# main.net
KiCad netlist of a schematic drawn in EAGLE
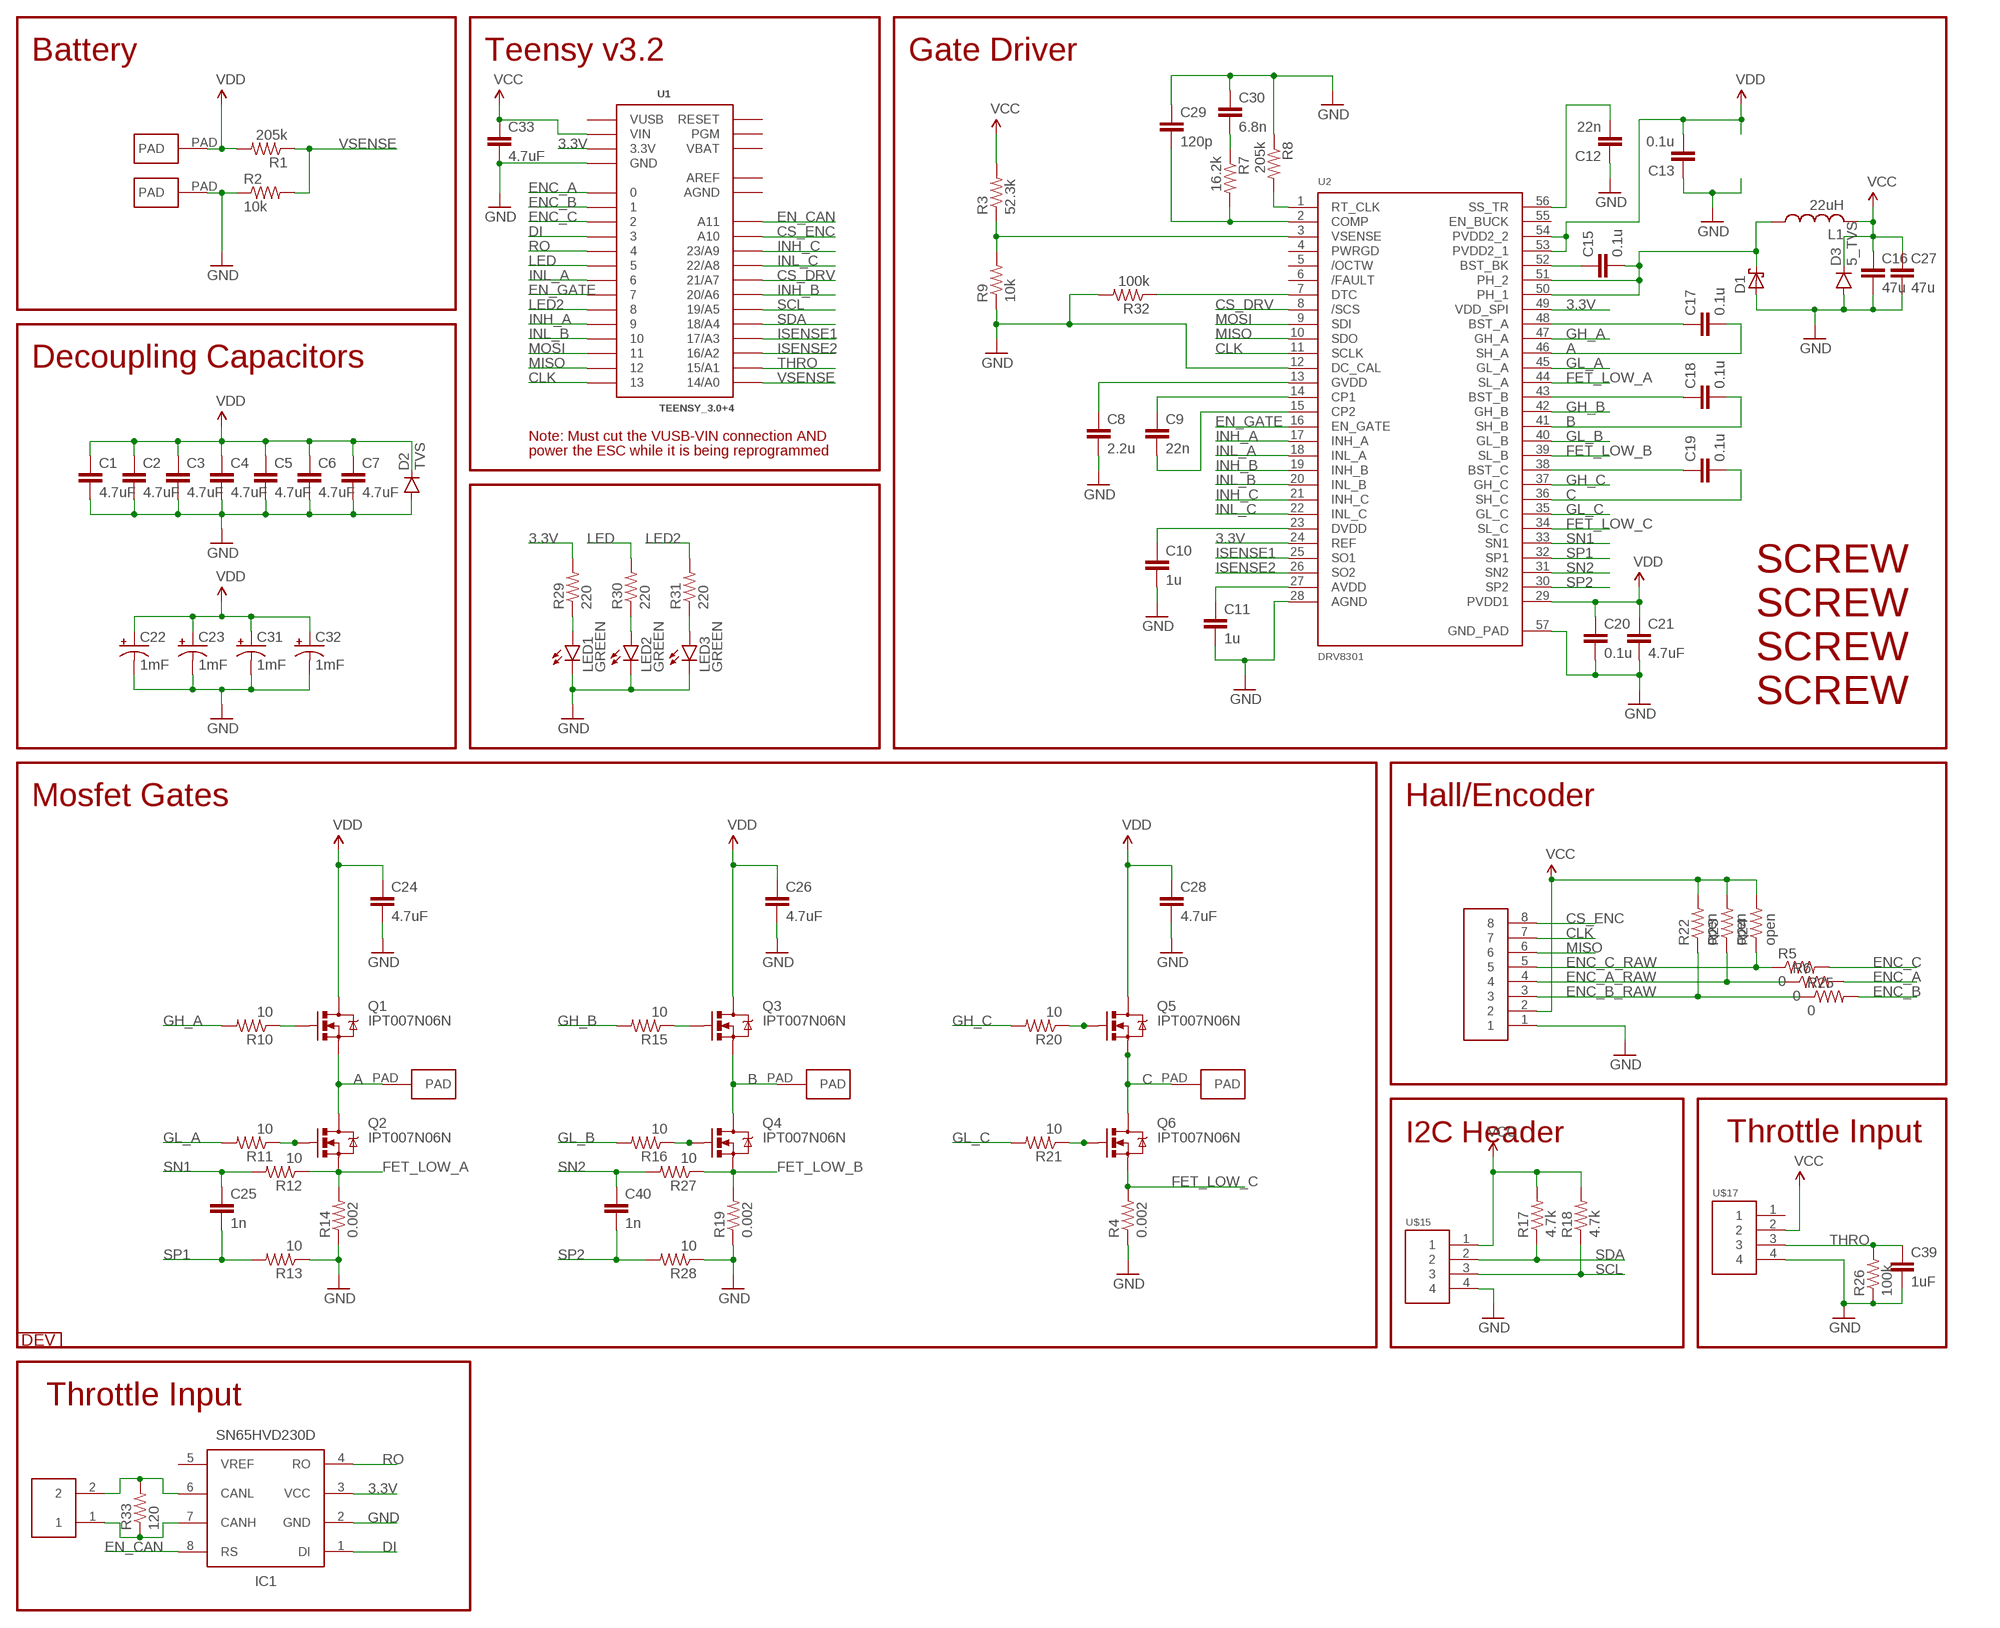
[diagram p0: schematic, sheet 1]

(export (version "E")
  (design (tool "Eeschema 10.0.6"))
  (components
    (comp (ref "C1")
      (value "4.7uF")
      (footprint "eagle-import:1206")
      (libsource (lib "eagle-import") (part "CAP1206"))
    )
    (comp (ref "C2")
      (value "4.7uF")
      (footprint "eagle-import:1206")
      (libsource (lib "eagle-import") (part "CAP1206"))
    )
    (comp (ref "C3")
      (value "4.7uF")
      (footprint "eagle-import:1206")
      (libsource (lib "eagle-import") (part "CAP1206"))
    )
    (comp (ref "C4")
      (value "4.7uF")
      (footprint "eagle-import:1206")
      (libsource (lib "eagle-import") (part "CAP1206"))
    )
    (comp (ref "C5")
      (value "4.7uF")
      (footprint "eagle-import:1206")
      (libsource (lib "eagle-import") (part "CAP1206"))
    )
    (comp (ref "C6")
      (value "4.7uF")
      (footprint "eagle-import:1206")
      (libsource (lib "eagle-import") (part "CAP1206"))
    )
    (comp (ref "C7")
      (value "4.7uF")
      (footprint "eagle-import:1206")
      (libsource (lib "eagle-import") (part "CAP1206"))
    )
    (comp (ref "C8")
      (value "2.2u")
      (footprint "eagle-import:0603-CAP")
      (libsource (lib "eagle-import") (part "SparkFun-Passives_CAP0603-CAP"))
    )
    (comp (ref "C9")
      (value "22n")
      (footprint "eagle-import:0603-CAP")
      (libsource (lib "eagle-import") (part "SparkFun-Passives_CAP0603-CAP"))
    )
    (comp (ref "C10")
      (value "1u")
      (footprint "eagle-import:0603-CAP")
      (libsource (lib "eagle-import") (part "CAP0603-CAP"))
    )
    (comp (ref "C11")
      (value "1u")
      (footprint "eagle-import:0603-CAP")
      (libsource (lib "eagle-import") (part "CAP0603-CAP"))
    )
    (comp (ref "C12")
      (value "22n")
      (footprint "eagle-import:0603-CAP")
      (libsource (lib "eagle-import") (part "SparkFun-Passives_CAP0603-CAP"))
    )
    (comp (ref "C13")
      (value "0.1u")
      (footprint "eagle-import:0603-CAP")
      (libsource (lib "eagle-import") (part "SparkFun-Passives_CAP0603-CAP"))
    )
    (comp (ref "C15")
      (value "0.1u")
      (footprint "eagle-import:0603-CAP")
      (libsource (lib "eagle-import") (part "SparkFun-Passives_CAP0603-CAP"))
    )
    (comp (ref "C16")
      (value "47u")
      (footprint "eagle-import:0805")
      (libsource (lib "eagle-import") (part "CAP0805"))
    )
    (comp (ref "C17")
      (value "0.1u")
      (footprint "eagle-import:0603-CAP")
      (libsource (lib "eagle-import") (part "SparkFun-Passives_CAP0603-CAP"))
    )
    (comp (ref "C18")
      (value "0.1u")
      (footprint "eagle-import:0603-CAP")
      (libsource (lib "eagle-import") (part "SparkFun-Passives_CAP0603-CAP"))
    )
    (comp (ref "C19")
      (value "0.1u")
      (footprint "eagle-import:0603-CAP")
      (libsource (lib "eagle-import") (part "SparkFun-Passives_CAP0603-CAP"))
    )
    (comp (ref "C20")
      (value "0.1u")
      (footprint "eagle-import:0603-CAP")
      (libsource (lib "eagle-import") (part "SparkFun-Passives_CAP0603-CAP"))
    )
    (comp (ref "C21")
      (value "4.7uF")
      (footprint "eagle-import:1206")
      (libsource (lib "eagle-import") (part "CAP1206"))
    )
    (comp (ref "C22")
      (value "1mF")
      (footprint "eagle-import:CPOL-RADIAL-1000UF-25V")
      (libsource (lib "eagle-import") (part "CAP_POLPTH4"))
    )
    (comp (ref "C23")
      (value "1mF")
      (footprint "eagle-import:CPOL-RADIAL-1000UF-25V")
      (libsource (lib "eagle-import") (part "CAP_POLPTH4"))
    )
    (comp (ref "C24")
      (value "4.7uF")
      (footprint "eagle-import:1206")
      (libsource (lib "eagle-import") (part "CAP1206"))
    )
    (comp (ref "C25")
      (value "1n")
      (footprint "eagle-import:0603-CAP")
      (libsource (lib "eagle-import") (part "SparkFun-Passives_CAP0603-CAP"))
    )
    (comp (ref "C26")
      (value "4.7uF")
      (footprint "eagle-import:1206")
      (libsource (lib "eagle-import") (part "CAP1206"))
    )
    (comp (ref "C27")
      (value "47u")
      (footprint "eagle-import:0805")
      (libsource (lib "eagle-import") (part "CAP0805"))
    )
    (comp (ref "C28")
      (value "4.7uF")
      (footprint "eagle-import:1206")
      (libsource (lib "eagle-import") (part "CAP1206"))
    )
    (comp (ref "C29")
      (value "120p")
      (footprint "eagle-import:0603-CAP")
      (libsource (lib "eagle-import") (part "SparkFun-Passives_CAP0603-CAP"))
    )
    (comp (ref "C30")
      (value "6.8n")
      (footprint "eagle-import:0603-CAP")
      (libsource (lib "eagle-import") (part "SparkFun-Passives_CAP0603-CAP"))
    )
    (comp (ref "C31")
      (value "1mF")
      (footprint "eagle-import:CPOL-RADIAL-1000UF-25V")
      (libsource (lib "eagle-import") (part "CAP_POLPTH4"))
    )
    (comp (ref "C32")
      (value "1mF")
      (footprint "eagle-import:CPOL-RADIAL-1000UF-25V")
      (libsource (lib "eagle-import") (part "CAP_POLPTH4"))
    )
    (comp (ref "C33")
      (value "4.7uF")
      (footprint "eagle-import:1206")
      (libsource (lib "eagle-import") (part "CAP1206"))
    )
    (comp (ref "C39")
      (value "1uF")
      (footprint "eagle-import:0603-CAP")
      (libsource (lib "eagle-import") (part "SparkFun-Passives_CAP0603-CAP"))
    )
    (comp (ref "C40")
      (value "1n")
      (footprint "eagle-import:0603-CAP")
      (libsource (lib "eagle-import") (part "SparkFun-Passives_CAP0603-CAP"))
    )
    (comp (ref "CAN")
      (value "HEADER2")
      (footprint "eagle-import:2PINVALULOK")
      (libsource (lib "eagle-import") (part "HEADER2"))
    )
    (comp (ref "D1")
      (value "SCHOTTKY_SMA")
      (footprint "eagle-import:SMA")
      (libsource (lib "eagle-import") (part "SCHOTTKY_SMA"))
    )
    (comp (ref "D2")
      (value "TVS")
      (footprint "eagle-import:SMC")
      (libsource (lib "eagle-import") (part "DIODEES3J"))
    )
    (comp (ref "D3")
      (value "5_TVS")
      (footprint "eagle-import:SOT23-3")
      (libsource (lib "eagle-import") (part "DIODESOT23"))
    )
    (comp (ref "IC1")
      (value "SN65HVD230D")
      (footprint "eagle-import:SO-8")
      (libsource (lib "eagle-import") (part "SN65HVD23D0"))
    )
    (comp (ref "L1")
      (value "22uH")
      (footprint "eagle-import:L5650M")
      (libsource (lib "eagle-import") (part "L-USL5650M"))
    )
    (comp (ref "LED1")
      (value "GREEN")
      (footprint "eagle-import:LED-1206")
      (libsource (lib "eagle-import") (part "LED1206"))
    )
    (comp (ref "LED2")
      (value "GREEN")
      (footprint "eagle-import:LED-1206")
      (libsource (lib "eagle-import") (part "LED1206"))
    )
    (comp (ref "LED3")
      (value "GREEN")
      (footprint "eagle-import:LED-1206")
      (libsource (lib "eagle-import") (part "LED1206"))
    )
    (comp (ref "Q1")
      (value "IPT007N06N")
      (footprint "eagle-import:PG-HSOF-8-1")
      (libsource (lib "eagle-import") (part "MOSFET-NCHANNELPG-HSOF-8-1"))
    )
    (comp (ref "Q2")
      (value "IPT007N06N")
      (footprint "eagle-import:PG-HSOF-8-1")
      (libsource (lib "eagle-import") (part "MOSFET-NCHANNELPG-HSOF-8-1"))
    )
    (comp (ref "Q3")
      (value "IPT007N06N")
      (footprint "eagle-import:PG-HSOF-8-1")
      (libsource (lib "eagle-import") (part "MOSFET-NCHANNELPG-HSOF-8-1"))
    )
    (comp (ref "Q4")
      (value "IPT007N06N")
      (footprint "eagle-import:PG-HSOF-8-1")
      (libsource (lib "eagle-import") (part "MOSFET-NCHANNELPG-HSOF-8-1"))
    )
    (comp (ref "Q5")
      (value "IPT007N06N")
      (footprint "eagle-import:PG-HSOF-8-1")
      (libsource (lib "eagle-import") (part "MOSFET-NCHANNELPG-HSOF-8-1"))
    )
    (comp (ref "Q6")
      (value "IPT007N06N")
      (footprint "eagle-import:PG-HSOF-8-1")
      (libsource (lib "eagle-import") (part "MOSFET-NCHANNELPG-HSOF-8-1"))
    )
    (comp (ref "R1")
      (value "205k")
      (footprint "eagle-import:0603-RES")
      (libsource (lib "eagle-import") (part "RESISTOR0603-RES"))
    )
    (comp (ref "R2")
      (value "10k")
      (footprint "eagle-import:0603-RES")
      (libsource (lib "eagle-import") (part "RESISTOR0603-RES"))
    )
    (comp (ref "R3")
      (value "52.3k")
      (footprint "eagle-import:0603-RES")
      (libsource (lib "eagle-import") (part "RESISTOR0603-RES"))
    )
    (comp (ref "R4")
      (value "0.002")
      (footprint "eagle-import:R2512")
      (libsource (lib "eagle-import") (part "SparkFun-Resistors_RESISTOR2512"))
    )
    (comp (ref "R5")
      (value "0")
      (footprint "eagle-import:0603-RES")
      (libsource (lib "eagle-import") (part "RESISTOR0603-RES"))
    )
    (comp (ref "R6")
      (value "0")
      (footprint "eagle-import:0603-RES")
      (libsource (lib "eagle-import") (part "RESISTOR0603-RES"))
    )
    (comp (ref "R7")
      (value "16.2k")
      (footprint "eagle-import:0603-RES")
      (libsource (lib "eagle-import") (part "RESISTOR0603-RES"))
    )
    (comp (ref "R8")
      (value "205k")
      (footprint "eagle-import:0603-RES")
      (libsource (lib "eagle-import") (part "RESISTOR0603-RES"))
    )
    (comp (ref "R9")
      (value "10k")
      (footprint "eagle-import:0603-RES")
      (libsource (lib "eagle-import") (part "RESISTOR0603-RES"))
    )
    (comp (ref "R10")
      (value "10")
      (footprint "eagle-import:0603-RES")
      (libsource (lib "eagle-import") (part "RESISTOR0603-RES"))
    )
    (comp (ref "R11")
      (value "10")
      (footprint "eagle-import:0603-RES")
      (libsource (lib "eagle-import") (part "RESISTOR0603-RES"))
    )
    (comp (ref "R12")
      (value "10")
      (footprint "eagle-import:0603-RES")
      (libsource (lib "eagle-import") (part "RESISTOR0603-RES"))
    )
    (comp (ref "R13")
      (value "10")
      (footprint "eagle-import:0603-RES")
      (libsource (lib "eagle-import") (part "RESISTOR0603-RES"))
    )
    (comp (ref "R14")
      (value "0.002")
      (footprint "eagle-import:R2512")
      (libsource (lib "eagle-import") (part "SparkFun-Resistors_RESISTOR2512"))
    )
    (comp (ref "R15")
      (value "10")
      (footprint "eagle-import:0603-RES")
      (libsource (lib "eagle-import") (part "RESISTOR0603-RES"))
    )
    (comp (ref "R16")
      (value "10")
      (footprint "eagle-import:0603-RES")
      (libsource (lib "eagle-import") (part "RESISTOR0603-RES"))
    )
    (comp (ref "R17")
      (value "4.7k")
      (footprint "eagle-import:0603-RES")
      (libsource (lib "eagle-import") (part "RESISTOR0603-RES"))
    )
    (comp (ref "R18")
      (value "4.7k")
      (footprint "eagle-import:0603-RES")
      (libsource (lib "eagle-import") (part "RESISTOR0603-RES"))
    )
    (comp (ref "R19")
      (value "0.002")
      (footprint "eagle-import:R2512")
      (libsource (lib "eagle-import") (part "SparkFun-Resistors_RESISTOR2512"))
    )
    (comp (ref "R20")
      (value "10")
      (footprint "eagle-import:0603-RES")
      (libsource (lib "eagle-import") (part "RESISTOR0603-RES"))
    )
    (comp (ref "R21")
      (value "10")
      (footprint "eagle-import:0603-RES")
      (libsource (lib "eagle-import") (part "RESISTOR0603-RES"))
    )
    (comp (ref "R22")
      (value "open")
      (footprint "eagle-import:0603-RES")
      (libsource (lib "eagle-import") (part "RESISTOR0603-RES"))
    )
    (comp (ref "R23")
      (value "open")
      (footprint "eagle-import:0603-RES")
      (libsource (lib "eagle-import") (part "RESISTOR0603-RES"))
    )
    (comp (ref "R24")
      (value "open")
      (footprint "eagle-import:0603-RES")
      (libsource (lib "eagle-import") (part "RESISTOR0603-RES"))
    )
    (comp (ref "R25")
      (value "0")
      (footprint "eagle-import:0603-RES")
      (libsource (lib "eagle-import") (part "RESISTOR0603-RES"))
    )
    (comp (ref "R26")
      (value "100k")
      (footprint "eagle-import:0603-RES")
      (libsource (lib "eagle-import") (part "RESISTOR0603-RES"))
    )
    (comp (ref "R27")
      (value "10")
      (footprint "eagle-import:0603-RES")
      (libsource (lib "eagle-import") (part "RESISTOR0603-RES"))
    )
    (comp (ref "R28")
      (value "10")
      (footprint "eagle-import:0603-RES")
      (libsource (lib "eagle-import") (part "RESISTOR0603-RES"))
    )
    (comp (ref "R29")
      (value "220")
      (footprint "eagle-import:0603-RES")
      (libsource (lib "eagle-import") (part "RESISTOR0603-RES"))
    )
    (comp (ref "R30")
      (value "220")
      (footprint "eagle-import:0603-RES")
      (libsource (lib "eagle-import") (part "RESISTOR0603-RES"))
    )
    (comp (ref "R31")
      (value "220")
      (footprint "eagle-import:0603-RES")
      (libsource (lib "eagle-import") (part "RESISTOR0603-RES"))
    )
    (comp (ref "R32")
      (value "100k")
      (footprint "eagle-import:0603-RES")
      (libsource (lib "eagle-import") (part "RESISTOR0603-RES"))
    )
    (comp (ref "R33")
      (value "120")
      (footprint "eagle-import:0603-RES")
      (libsource (lib "eagle-import") (part "RESISTOR0603-RES"))
    )
    (comp (ref "U$2")
      (value "HEADER8")
      (footprint "eagle-import:8PINVALULOK")
      (libsource (lib "eagle-import") (part "HEADER8"))
    )
    (comp (ref "U$15")
      (value "HEADER4VALULOK")
      (footprint "eagle-import:4PINVALULOK")
      (libsource (lib "eagle-import") (part "HEADER4VALULOK"))
    )
    (comp (ref "U$16")
      (value "DEV")
      (footprint "eagle-import:DEV")
      (libsource (lib "eagle-import") (part "DEV"))
    )
    (comp (ref "U$17")
      (value "HEADER4VALULOK")
      (footprint "eagle-import:4PINVALULOK")
      (libsource (lib "eagle-import") (part "HEADER4VALULOK"))
    )
    (comp (ref "U$19")
      (value "SCREW")
      (footprint "eagle-import:M3HOLE")
      (libsource (lib "eagle-import") (part "SCREW"))
    )
    (comp (ref "U$20")
      (value "SCREW")
      (footprint "eagle-import:M3HOLE")
      (libsource (lib "eagle-import") (part "SCREW"))
    )
    (comp (ref "U$21")
      (value "SCREW")
      (footprint "eagle-import:M3HOLE")
      (libsource (lib "eagle-import") (part "SCREW"))
    )
    (comp (ref "U$22")
      (value "SCREW")
      (footprint "eagle-import:M3HOLE")
      (libsource (lib "eagle-import") (part "SCREW"))
    )
    (comp (ref "U$23")
      (value "PAD")
      (footprint "eagle-import:PAD")
      (libsource (lib "eagle-import") (part "PAD"))
    )
    (comp (ref "U$24")
      (value "PAD")
      (footprint "eagle-import:PAD")
      (libsource (lib "eagle-import") (part "PAD"))
    )
    (comp (ref "U$25")
      (value "PAD")
      (footprint "eagle-import:PAD")
      (libsource (lib "eagle-import") (part "PAD"))
    )
    (comp (ref "U$26")
      (value "PAD")
      (footprint "eagle-import:PAD")
      (libsource (lib "eagle-import") (part "PAD"))
    )
    (comp (ref "U$27")
      (value "PAD")
      (footprint "eagle-import:PAD")
      (libsource (lib "eagle-import") (part "PAD"))
    )
    (comp (ref "U1")
      (value "TEENSY_3.0+4")
      (footprint "eagle-import:TEENSY_3.0+4")
      (libsource (lib "eagle-import") (part "TEENSY_3.0+4"))
    )
    (comp (ref "U2")
      (value "DRV8301")
      (footprint "eagle-import:DRV8301")
      (libsource (lib "eagle-import") (part "DRV8301"))
    )
  )
  (nets
    (net (code "1") (name "/3.3V") (class "Default")
      (node (ref "IC1") (pin "3") (pinfunction "VCC_3") (pintype "power_in"))
      (node (ref "R29") (pin "2") (pinfunction "2_2") (pintype "passive"))
      (node (ref "U1") (pin "3.3V") (pinfunction "3.3V_3.3V") (pintype "power_in"))
      (node (ref "U1") (pin "3.3V1") (pinfunction "3.3V_3.3V1") (pintype "power_in"))
      (node (ref "U2") (pin "24") (pinfunction "REF_24") (pintype "bidirectional"))
      (node (ref "U2") (pin "49") (pinfunction "VDD_SPI_49") (pintype "bidirectional"))
    )
    (net (code "2") (name "/A") (class "Default")
      (node (ref "C17") (pin "2") (pinfunction "2_2") (pintype "passive"))
      (node (ref "Q1") (pin "S") (pinfunction "S_S") (pintype "passive"))
      (node (ref "Q2") (pin "D") (pinfunction "D_D") (pintype "passive"))
      (node (ref "U$23") (pin "PAD") (pinfunction "PAD_PAD") (pintype "bidirectional"))
      (node (ref "U2") (pin "46") (pinfunction "SH_A_46") (pintype "bidirectional"))
    )
    (net (code "3") (name "/AGND") (class "Default")
      (node (ref "U1") (pin "AGND") (pinfunction "AGND_AGND") (pintype "power_in"))
    )
    (net (code "4") (name "/AREF") (class "Default")
      (node (ref "U1") (pin "AREF") (pinfunction "AREF_AREF") (pintype "power_in"))
    )
    (net (code "5") (name "/B") (class "Default")
      (node (ref "C18") (pin "2") (pinfunction "2_2") (pintype "passive"))
      (node (ref "Q3") (pin "S") (pinfunction "S_S") (pintype "passive"))
      (node (ref "Q4") (pin "D") (pinfunction "D_D") (pintype "passive"))
      (node (ref "U$24") (pin "PAD") (pinfunction "PAD_PAD") (pintype "bidirectional"))
      (node (ref "U2") (pin "41") (pinfunction "SH_B_41") (pintype "bidirectional"))
    )
    (net (code "6") (name "/C") (class "Default")
      (node (ref "C19") (pin "2") (pinfunction "2_2") (pintype "passive"))
      (node (ref "Q5") (pin "S") (pinfunction "S_S") (pintype "passive"))
      (node (ref "Q6") (pin "D") (pinfunction "D_D") (pintype "passive"))
      (node (ref "U$25") (pin "PAD") (pinfunction "PAD_PAD") (pintype "bidirectional"))
      (node (ref "U2") (pin "36") (pinfunction "SH_C_36") (pintype "bidirectional"))
    )
    (net (code "7") (name "/CLK") (class "Default")
      (node (ref "U$2") (pin "7") (pinfunction "7_7") (pintype "bidirectional"))
      (node (ref "U1") (pin "13") (pinfunction "13_13") (pintype "bidirectional"))
      (node (ref "U2") (pin "11") (pinfunction "SCLK_11") (pintype "bidirectional"))
    )
    (net (code "8") (name "/CS_DRV") (class "Default")
      (node (ref "U1") (pin "21/A7") (pinfunction "21/A7_21/A7") (pintype "bidirectional"))
      (node (ref "U2") (pin "8") (pinfunction "/SCS_8") (pintype "bidirectional"))
    )
    (net (code "9") (name "/CS_ENC") (class "Default")
      (node (ref "U$2") (pin "8") (pinfunction "8_8") (pintype "bidirectional"))
      (node (ref "U1") (pin "A10") (pinfunction "A10_A10") (pintype "bidirectional"))
    )
    (net (code "10") (name "/DI") (class "Default")
      (node (ref "IC1") (pin "1") (pinfunction "DI_1") (pintype "input"))
      (node (ref "U1") (pin "3") (pinfunction "3_3") (pintype "bidirectional"))
    )
    (net (code "11") (name "/ENC_A") (class "Default")
      (node (ref "R6") (pin "2") (pinfunction "2_2") (pintype "passive"))
      (node (ref "U1") (pin "0") (pinfunction "0_0") (pintype "bidirectional"))
    )
    (net (code "12") (name "/ENC_A_RAW") (class "Default")
      (node (ref "R23") (pin "1") (pinfunction "1_1") (pintype "passive"))
      (node (ref "R6") (pin "1") (pinfunction "1_1") (pintype "passive"))
      (node (ref "U$2") (pin "4") (pinfunction "4_4") (pintype "bidirectional"))
    )
    (net (code "13") (name "/ENC_B") (class "Default")
      (node (ref "R25") (pin "2") (pinfunction "2_2") (pintype "passive"))
      (node (ref "U1") (pin "1") (pinfunction "1_1") (pintype "bidirectional"))
    )
    (net (code "14") (name "/ENC_B_RAW") (class "Default")
      (node (ref "R22") (pin "1") (pinfunction "1_1") (pintype "passive"))
      (node (ref "R25") (pin "1") (pinfunction "1_1") (pintype "passive"))
      (node (ref "U$2") (pin "3") (pinfunction "3_3") (pintype "bidirectional"))
    )
    (net (code "15") (name "/ENC_C") (class "Default")
      (node (ref "R5") (pin "2") (pinfunction "2_2") (pintype "passive"))
      (node (ref "U1") (pin "2") (pinfunction "2_2") (pintype "bidirectional"))
    )
    (net (code "16") (name "/ENC_C_RAW") (class "Default")
      (node (ref "R24") (pin "1") (pinfunction "1_1") (pintype "passive"))
      (node (ref "R5") (pin "1") (pinfunction "1_1") (pintype "passive"))
      (node (ref "U$2") (pin "5") (pinfunction "5_5") (pintype "bidirectional"))
    )
    (net (code "17") (name "/EN_CAN") (class "Default")
      (node (ref "IC1") (pin "8") (pinfunction "RS_8") (pintype "input"))
      (node (ref "U1") (pin "A11") (pinfunction "A11_A11") (pintype "bidirectional"))
    )
    (net (code "18") (name "/EN_GATE") (class "Default")
      (node (ref "U1") (pin "7") (pinfunction "7_7") (pintype "bidirectional"))
      (node (ref "U2") (pin "16") (pinfunction "EN_GATE_16") (pintype "bidirectional"))
    )
    (net (code "19") (name "/FET_LOW_A") (class "Default")
      (node (ref "Q2") (pin "S") (pinfunction "S_S") (pintype "passive"))
      (node (ref "R12") (pin "1") (pinfunction "1_1") (pintype "passive"))
      (node (ref "R14") (pin "2") (pinfunction "2_2") (pintype "passive"))
      (node (ref "U2") (pin "44") (pinfunction "SL_A_44") (pintype "bidirectional"))
    )
    (net (code "20") (name "/FET_LOW_B") (class "Default")
      (node (ref "Q4") (pin "S") (pinfunction "S_S") (pintype "passive"))
      (node (ref "R19") (pin "2") (pinfunction "2_2") (pintype "passive"))
      (node (ref "R27") (pin "1") (pinfunction "1_1") (pintype "passive"))
      (node (ref "U2") (pin "39") (pinfunction "SL_B_39") (pintype "bidirectional"))
    )
    (net (code "21") (name "/FET_LOW_C") (class "Default")
      (node (ref "Q6") (pin "S") (pinfunction "S_S") (pintype "passive"))
      (node (ref "R4") (pin "2") (pinfunction "2_2") (pintype "passive"))
      (node (ref "U2") (pin "34") (pinfunction "SL_C_34") (pintype "bidirectional"))
    )
    (net (code "22") (name "/GH_A") (class "Default")
      (node (ref "R10") (pin "2") (pinfunction "2_2") (pintype "passive"))
      (node (ref "U2") (pin "47") (pinfunction "GH_A_47") (pintype "bidirectional"))
    )
    (net (code "23") (name "/GH_B") (class "Default")
      (node (ref "R15") (pin "2") (pinfunction "2_2") (pintype "passive"))
      (node (ref "U2") (pin "42") (pinfunction "GH_B_42") (pintype "bidirectional"))
    )
    (net (code "24") (name "/GH_C") (class "Default")
      (node (ref "R20") (pin "2") (pinfunction "2_2") (pintype "passive"))
      (node (ref "U2") (pin "37") (pinfunction "GH_C_37") (pintype "bidirectional"))
    )
    (net (code "25") (name "/GL_A") (class "Default")
      (node (ref "R11") (pin "2") (pinfunction "2_2") (pintype "passive"))
      (node (ref "U2") (pin "45") (pinfunction "GL_A_45") (pintype "bidirectional"))
    )
    (net (code "26") (name "/GL_B") (class "Default")
      (node (ref "R16") (pin "2") (pinfunction "2_2") (pintype "passive"))
      (node (ref "U2") (pin "40") (pinfunction "GL_B_40") (pintype "bidirectional"))
    )
    (net (code "27") (name "/GL_C") (class "Default")
      (node (ref "R21") (pin "2") (pinfunction "2_2") (pintype "passive"))
      (node (ref "U2") (pin "35") (pinfunction "GL_C_35") (pintype "bidirectional"))
    )
    (net (code "28") (name "/INH_A") (class "Default")
      (node (ref "U1") (pin "9") (pinfunction "9_9") (pintype "bidirectional"))
      (node (ref "U2") (pin "17") (pinfunction "INH_A_17") (pintype "bidirectional"))
    )
    (net (code "29") (name "/INH_B") (class "Default")
      (node (ref "U1") (pin "20/A6") (pinfunction "20/A6_20/A6") (pintype "bidirectional"))
      (node (ref "U2") (pin "19") (pinfunction "INH_B_19") (pintype "bidirectional"))
    )
    (net (code "30") (name "/INH_C") (class "Default")
      (node (ref "U1") (pin "23/A9") (pinfunction "23/A9_23/A9") (pintype "bidirectional"))
      (node (ref "U2") (pin "21") (pinfunction "INH_C_21") (pintype "bidirectional"))
    )
    (net (code "31") (name "/INL_A") (class "Default")
      (node (ref "U1") (pin "6") (pinfunction "6_6") (pintype "bidirectional"))
      (node (ref "U2") (pin "18") (pinfunction "INL_A_18") (pintype "bidirectional"))
    )
    (net (code "32") (name "/INL_B") (class "Default")
      (node (ref "U1") (pin "10") (pinfunction "10_10") (pintype "bidirectional"))
      (node (ref "U2") (pin "20") (pinfunction "INL_B_20") (pintype "bidirectional"))
    )
    (net (code "33") (name "/INL_C") (class "Default")
      (node (ref "U1") (pin "22/A8") (pinfunction "22/A8_22/A8") (pintype "bidirectional"))
      (node (ref "U2") (pin "22") (pinfunction "INL_C_22") (pintype "bidirectional"))
    )
    (net (code "34") (name "/ISENSE1") (class "Default")
      (node (ref "U1") (pin "17/A3") (pinfunction "17/A3_17/A3") (pintype "bidirectional"))
      (node (ref "U2") (pin "25") (pinfunction "SO1_25") (pintype "bidirectional"))
    )
    (net (code "35") (name "/ISENSE2") (class "Default")
      (node (ref "U1") (pin "16/A2") (pinfunction "16/A2_16/A2") (pintype "bidirectional"))
      (node (ref "U2") (pin "26") (pinfunction "SO2_26") (pintype "bidirectional"))
    )
    (net (code "36") (name "/LED") (class "Default")
      (node (ref "R30") (pin "2") (pinfunction "2_2") (pintype "passive"))
      (node (ref "U1") (pin "5") (pinfunction "5_5") (pintype "bidirectional"))
    )
    (net (code "37") (name "/LED2") (class "Default")
      (node (ref "R31") (pin "2") (pinfunction "2_2") (pintype "passive"))
      (node (ref "U1") (pin "8") (pinfunction "8_8") (pintype "bidirectional"))
    )
    (net (code "38") (name "/MISO") (class "Default")
      (node (ref "U$2") (pin "6") (pinfunction "6_6") (pintype "bidirectional"))
      (node (ref "U1") (pin "12") (pinfunction "12_12") (pintype "bidirectional"))
      (node (ref "U2") (pin "10") (pinfunction "SDO_10") (pintype "bidirectional"))
    )
    (net (code "39") (name "/MOSI") (class "Default")
      (node (ref "U1") (pin "11") (pinfunction "11_11") (pintype "bidirectional"))
      (node (ref "U2") (pin "9") (pinfunction "SDI_9") (pintype "bidirectional"))
    )
    (net (code "40") (name "/RO") (class "Default")
      (node (ref "IC1") (pin "4") (pinfunction "RO_4") (pintype "output"))
      (node (ref "U1") (pin "4") (pinfunction "4_4") (pintype "bidirectional"))
    )
    (net (code "41") (name "/SCL") (class "Default")
      (node (ref "R18") (pin "1") (pinfunction "1_1") (pintype "passive"))
      (node (ref "U$15") (pin "3") (pinfunction "3_3") (pintype "bidirectional"))
      (node (ref "U1") (pin "19/A5") (pinfunction "19/A5_19/A5") (pintype "bidirectional"))
    )
    (net (code "42") (name "/SDA") (class "Default")
      (node (ref "R17") (pin "1") (pinfunction "1_1") (pintype "passive"))
      (node (ref "U$15") (pin "2") (pinfunction "2_2") (pintype "bidirectional"))
      (node (ref "U1") (pin "18/A4") (pinfunction "18/A4_18/A4") (pintype "bidirectional"))
    )
    (net (code "43") (name "/SN1") (class "Default")
      (node (ref "C25") (pin "1") (pinfunction "1_1") (pintype "passive"))
      (node (ref "R12") (pin "2") (pinfunction "2_2") (pintype "passive"))
      (node (ref "U2") (pin "33") (pinfunction "SN1_33") (pintype "bidirectional"))
    )
    (net (code "44") (name "/SN2") (class "Default")
      (node (ref "C40") (pin "1") (pinfunction "1_1") (pintype "passive"))
      (node (ref "R27") (pin "2") (pinfunction "2_2") (pintype "passive"))
      (node (ref "U2") (pin "31") (pinfunction "SN2_31") (pintype "bidirectional"))
    )
    (net (code "45") (name "/SP1") (class "Default")
      (node (ref "C25") (pin "2") (pinfunction "2_2") (pintype "passive"))
      (node (ref "R13") (pin "2") (pinfunction "2_2") (pintype "passive"))
      (node (ref "U2") (pin "32") (pinfunction "SP1_32") (pintype "bidirectional"))
    )
    (net (code "46") (name "/SP2") (class "Default")
      (node (ref "C40") (pin "2") (pinfunction "2_2") (pintype "passive"))
      (node (ref "R28") (pin "2") (pinfunction "2_2") (pintype "passive"))
      (node (ref "U2") (pin "30") (pinfunction "SP2_30") (pintype "bidirectional"))
    )
    (net (code "47") (name "/THRO") (class "Default")
      (node (ref "C39") (pin "1") (pinfunction "1_1") (pintype "passive"))
      (node (ref "R26") (pin "2") (pinfunction "2_2") (pintype "passive"))
      (node (ref "U$17") (pin "3") (pinfunction "3_3") (pintype "bidirectional"))
      (node (ref "U1") (pin "15/A1") (pinfunction "15/A1_15/A1") (pintype "bidirectional"))
    )
    (net (code "48") (name "/VBAT") (class "Default")
      (node (ref "U1") (pin "VBAT") (pinfunction "VBAT_VBAT") (pintype "power_in"))
    )
    (net (code "49") (name "/VSENSE") (class "Default")
      (node (ref "R1") (pin "1") (pinfunction "1_1") (pintype "passive"))
      (node (ref "R2") (pin "2") (pinfunction "2_2") (pintype "passive"))
      (node (ref "U1") (pin "14/A0") (pinfunction "14/A0_14/A0") (pintype "bidirectional"))
    )
    (net (code "50") (name "/VUSB") (class "Default")
      (node (ref "U1") (pin "VUSB") (pinfunction "VUSB_VUSB") (pintype "power_in"))
    )
    (net (code "51") (name "GND") (class "Default")
      (node (ref "C1") (pin "2") (pinfunction "2_2") (pintype "passive"))
      (node (ref "C10") (pin "2") (pinfunction "2_2") (pintype "passive"))
      (node (ref "C11") (pin "2") (pinfunction "2_2") (pintype "passive"))
      (node (ref "C12") (pin "1") (pinfunction "1_1") (pintype "passive"))
      (node (ref "C13") (pin "1") (pinfunction "1_1") (pintype "passive"))
      (node (ref "C16") (pin "2") (pinfunction "2_2") (pintype "passive"))
      (node (ref "C2") (pin "2") (pinfunction "2_2") (pintype "passive"))
      (node (ref "C20") (pin "2") (pinfunction "2_2") (pintype "passive"))
      (node (ref "C21") (pin "2") (pinfunction "2_2") (pintype "passive"))
      (node (ref "C22") (pin "-") (pinfunction "-_-") (pintype "passive"))
      (node (ref "C23") (pin "-") (pinfunction "-_-") (pintype "passive"))
      (node (ref "C24") (pin "2") (pinfunction "2_2") (pintype "passive"))
      (node (ref "C26") (pin "2") (pinfunction "2_2") (pintype "passive"))
      (node (ref "C27") (pin "2") (pinfunction "2_2") (pintype "passive"))
      (node (ref "C28") (pin "2") (pinfunction "2_2") (pintype "passive"))
      (node (ref "C29") (pin "1") (pinfunction "1_1") (pintype "passive"))
      (node (ref "C3") (pin "2") (pinfunction "2_2") (pintype "passive"))
      (node (ref "C30") (pin "1") (pinfunction "1_1") (pintype "passive"))
      (node (ref "C31") (pin "-") (pinfunction "-_-") (pintype "passive"))
      (node (ref "C32") (pin "-") (pinfunction "-_-") (pintype "passive"))
      (node (ref "C33") (pin "2") (pinfunction "2_2") (pintype "passive"))
      (node (ref "C39") (pin "2") (pinfunction "2_2") (pintype "passive"))
      (node (ref "C4") (pin "2") (pinfunction "2_2") (pintype "passive"))
      (node (ref "C5") (pin "2") (pinfunction "2_2") (pintype "passive"))
      (node (ref "C6") (pin "2") (pinfunction "2_2") (pintype "passive"))
      (node (ref "C7") (pin "2") (pinfunction "2_2") (pintype "passive"))
      (node (ref "C8") (pin "2") (pinfunction "2_2") (pintype "passive"))
      (node (ref "D1") (pin "A") (pinfunction "A_A") (pintype "passive"))
      (node (ref "D2") (pin "A") (pinfunction "A_A") (pintype "passive"))
      (node (ref "D3") (pin "1") (pinfunction "A_1") (pintype "passive"))
      (node (ref "IC1") (pin "2") (pinfunction "GND_2") (pintype "power_in"))
      (node (ref "LED1") (pin "C") (pinfunction "C_C") (pintype "passive"))
      (node (ref "LED2") (pin "C") (pinfunction "C_C") (pintype "passive"))
      (node (ref "LED3") (pin "C") (pinfunction "C_C") (pintype "passive"))
      (node (ref "R13") (pin "1") (pinfunction "1_1") (pintype "passive"))
      (node (ref "R14") (pin "1") (pinfunction "1_1") (pintype "passive"))
      (node (ref "R19") (pin "1") (pinfunction "1_1") (pintype "passive"))
      (node (ref "R2") (pin "1") (pinfunction "1_1") (pintype "passive"))
      (node (ref "R26") (pin "1") (pinfunction "1_1") (pintype "passive"))
      (node (ref "R28") (pin "1") (pinfunction "1_1") (pintype "passive"))
      (node (ref "R32") (pin "2") (pinfunction "2_2") (pintype "passive"))
      (node (ref "R4") (pin "1") (pinfunction "1_1") (pintype "passive"))
      (node (ref "R8") (pin "1") (pinfunction "1_1") (pintype "passive"))
      (node (ref "R9") (pin "1") (pinfunction "1_1") (pintype "passive"))
      (node (ref "U$15") (pin "4") (pinfunction "4_4") (pintype "bidirectional"))
      (node (ref "U$17") (pin "4") (pinfunction "4_4") (pintype "bidirectional"))
      (node (ref "U$2") (pin "1") (pinfunction "1_1") (pintype "bidirectional"))
      (node (ref "U$27") (pin "PAD") (pinfunction "PAD_PAD") (pintype "bidirectional"))
      (node (ref "U1") (pin "GND") (pinfunction "GND_GND") (pintype "power_in"))
      (node (ref "U1") (pin "GND1") (pinfunction "GND_GND1") (pintype "power_in"))
      (node (ref "U2") (pin "12") (pinfunction "DC_CAL_12") (pintype "bidirectional"))
      (node (ref "U2") (pin "28") (pinfunction "AGND_28") (pintype "bidirectional"))
      (node (ref "U2") (pin "57") (pinfunction "GND_PAD_57") (pintype "bidirectional"))
    )
    (net (code "52") (name "Net-(C30-Pad2)") (class "Default")
      (node (ref "C30") (pin "2") (pinfunction "2_2") (pintype "passive"))
      (node (ref "R7") (pin "1") (pinfunction "1_1") (pintype "passive"))
    )
    (net (code "53") (name "Net-(IC1-CANH)") (class "Default")
      (node (ref "CAN") (pin "1") (pinfunction "1_1") (pintype "bidirectional"))
      (node (ref "IC1") (pin "7") (pinfunction "CANH_7") (pintype "bidirectional"))
      (node (ref "R33") (pin "1") (pinfunction "1_1") (pintype "passive"))
    )
    (net (code "54") (name "Net-(IC1-CANL)") (class "Default")
      (node (ref "CAN") (pin "2") (pinfunction "2_2") (pintype "bidirectional"))
      (node (ref "IC1") (pin "6") (pinfunction "CANL_6") (pintype "bidirectional"))
      (node (ref "R33") (pin "2") (pinfunction "2_2") (pintype "passive"))
    )
    (net (code "55") (name "Net-(LED1-PadA)") (class "Default")
      (node (ref "LED1") (pin "A") (pinfunction "A_A") (pintype "passive"))
      (node (ref "R29") (pin "1") (pinfunction "1_1") (pintype "passive"))
    )
    (net (code "56") (name "Net-(LED2-PadA)") (class "Default")
      (node (ref "LED2") (pin "A") (pinfunction "A_A") (pintype "passive"))
      (node (ref "R30") (pin "1") (pinfunction "1_1") (pintype "passive"))
    )
    (net (code "57") (name "Net-(LED3-PadA)") (class "Default")
      (node (ref "LED3") (pin "A") (pinfunction "A_A") (pintype "passive"))
      (node (ref "R31") (pin "1") (pinfunction "1_1") (pintype "passive"))
    )
    (net (code "58") (name "Net-(Q1-PadG)") (class "Default")
      (node (ref "Q1") (pin "G") (pinfunction "G_G") (pintype "passive"))
      (node (ref "R10") (pin "1") (pinfunction "1_1") (pintype "passive"))
    )
    (net (code "59") (name "Net-(Q2-PadG)") (class "Default")
      (node (ref "Q2") (pin "G") (pinfunction "G_G") (pintype "passive"))
      (node (ref "R11") (pin "1") (pinfunction "1_1") (pintype "passive"))
    )
    (net (code "60") (name "Net-(Q3-PadG)") (class "Default")
      (node (ref "Q3") (pin "G") (pinfunction "G_G") (pintype "passive"))
      (node (ref "R15") (pin "1") (pinfunction "1_1") (pintype "passive"))
    )
    (net (code "61") (name "Net-(Q4-PadG)") (class "Default")
      (node (ref "Q4") (pin "G") (pinfunction "G_G") (pintype "passive"))
      (node (ref "R16") (pin "1") (pinfunction "1_1") (pintype "passive"))
    )
    (net (code "62") (name "Net-(Q5-PadG)") (class "Default")
      (node (ref "Q5") (pin "G") (pinfunction "G_G") (pintype "passive"))
      (node (ref "R20") (pin "1") (pinfunction "1_1") (pintype "passive"))
    )
    (net (code "63") (name "Net-(Q6-PadG)") (class "Default")
      (node (ref "Q6") (pin "G") (pinfunction "G_G") (pintype "passive"))
      (node (ref "R21") (pin "1") (pinfunction "1_1") (pintype "passive"))
    )
    (net (code "64") (name "Net-(U2-AVDD)") (class "Default")
      (node (ref "C11") (pin "1") (pinfunction "1_1") (pintype "passive"))
      (node (ref "U2") (pin "27") (pinfunction "AVDD_27") (pintype "bidirectional"))
    )
    (net (code "65") (name "Net-(U2-BST_A)") (class "Default")
      (node (ref "C17") (pin "1") (pinfunction "1_1") (pintype "passive"))
      (node (ref "U2") (pin "48") (pinfunction "BST_A_48") (pintype "bidirectional"))
    )
    (net (code "66") (name "Net-(U2-BST_B)") (class "Default")
      (node (ref "C18") (pin "1") (pinfunction "1_1") (pintype "passive"))
      (node (ref "U2") (pin "43") (pinfunction "BST_B_43") (pintype "bidirectional"))
    )
    (net (code "67") (name "Net-(U2-BST_BK)") (class "Default")
      (node (ref "C15") (pin "1") (pinfunction "1_1") (pintype "passive"))
      (node (ref "U2") (pin "52") (pinfunction "BST_BK_52") (pintype "bidirectional"))
    )
    (net (code "68") (name "Net-(U2-BST_C)") (class "Default")
      (node (ref "C19") (pin "1") (pinfunction "1_1") (pintype "passive"))
      (node (ref "U2") (pin "38") (pinfunction "BST_C_38") (pintype "bidirectional"))
    )
    (net (code "69") (name "Net-(U2-COMP)") (class "Default")
      (node (ref "C29") (pin "2") (pinfunction "2_2") (pintype "passive"))
      (node (ref "R7") (pin "2") (pinfunction "2_2") (pintype "passive"))
      (node (ref "U2") (pin "2") (pinfunction "COMP_2") (pintype "bidirectional"))
    )
    (net (code "70") (name "Net-(U2-CP1)") (class "Default")
      (node (ref "C9") (pin "1") (pinfunction "1_1") (pintype "passive"))
      (node (ref "U2") (pin "14") (pinfunction "CP1_14") (pintype "bidirectional"))
    )
    (net (code "71") (name "Net-(U2-CP2)") (class "Default")
      (node (ref "C9") (pin "2") (pinfunction "2_2") (pintype "passive"))
      (node (ref "U2") (pin "15") (pinfunction "CP2_15") (pintype "bidirectional"))
    )
    (net (code "72") (name "Net-(U2-DTC)") (class "Default")
      (node (ref "R32") (pin "1") (pinfunction "1_1") (pintype "passive"))
      (node (ref "U2") (pin "7") (pinfunction "DTC_7") (pintype "bidirectional"))
    )
    (net (code "73") (name "Net-(U2-DVDD)") (class "Default")
      (node (ref "C10") (pin "1") (pinfunction "1_1") (pintype "passive"))
      (node (ref "U2") (pin "23") (pinfunction "DVDD_23") (pintype "bidirectional"))
    )
    (net (code "74") (name "Net-(U2-GVDD)") (class "Default")
      (node (ref "C8") (pin "1") (pinfunction "1_1") (pintype "passive"))
      (node (ref "U2") (pin "13") (pinfunction "GVDD_13") (pintype "bidirectional"))
    )
    (net (code "75") (name "Net-(U2-PH_1)") (class "Default")
      (node (ref "C15") (pin "2") (pinfunction "2_2") (pintype "passive"))
      (node (ref "D1") (pin "C") (pinfunction "C_C") (pintype "passive"))
      (node (ref "L1") (pin "1") (pinfunction "1_1") (pintype "passive"))
      (node (ref "U2") (pin "50") (pinfunction "PH_1_50") (pintype "bidirectional"))
      (node (ref "U2") (pin "51") (pinfunction "PH_2_51") (pintype "bidirectional"))
    )
    (net (code "76") (name "Net-(U2-RT_CLK)") (class "Default")
      (node (ref "R8") (pin "2") (pinfunction "2_2") (pintype "passive"))
      (node (ref "U2") (pin "1") (pinfunction "RT_CLK_1") (pintype "bidirectional"))
    )
    (net (code "77") (name "Net-(U2-SS_TR)") (class "Default")
      (node (ref "C12") (pin "2") (pinfunction "2_2") (pintype "passive"))
      (node (ref "U2") (pin "56") (pinfunction "SS_TR_56") (pintype "bidirectional"))
    )
    (net (code "78") (name "Net-(U2-VSENSE)") (class "Default")
      (node (ref "R3") (pin "1") (pinfunction "1_1") (pintype "passive"))
      (node (ref "R9") (pin "2") (pinfunction "2_2") (pintype "passive"))
      (node (ref "U2") (pin "3") (pinfunction "VSENSE_3") (pintype "bidirectional"))
    )
    (net (code "79") (name "VCC") (class "Default")
      (node (ref "C16") (pin "1") (pinfunction "1_1") (pintype "passive"))
      (node (ref "C27") (pin "1") (pinfunction "1_1") (pintype "passive"))
      (node (ref "C33") (pin "1") (pinfunction "1_1") (pintype "passive"))
      (node (ref "D3") (pin "3") (pinfunction "C_3") (pintype "passive"))
      (node (ref "L1") (pin "2") (pinfunction "2_2") (pintype "passive"))
      (node (ref "R17") (pin "2") (pinfunction "2_2") (pintype "passive"))
      (node (ref "R18") (pin "2") (pinfunction "2_2") (pintype "passive"))
      (node (ref "R22") (pin "2") (pinfunction "2_2") (pintype "passive"))
      (node (ref "R23") (pin "2") (pinfunction "2_2") (pintype "passive"))
      (node (ref "R24") (pin "2") (pinfunction "2_2") (pintype "passive"))
      (node (ref "R3") (pin "2") (pinfunction "2_2") (pintype "passive"))
      (node (ref "U$15") (pin "1") (pinfunction "1_1") (pintype "bidirectional"))
      (node (ref "U$17") (pin "2") (pinfunction "2_2") (pintype "bidirectional"))
      (node (ref "U$2") (pin "2") (pinfunction "2_2") (pintype "bidirectional"))
      (node (ref "U1") (pin "VIN") (pinfunction "VIN_VIN") (pintype "power_in"))
    )
    (net (code "80") (name "VDD") (class "Default")
      (node (ref "C1") (pin "1") (pinfunction "1_1") (pintype "passive"))
      (node (ref "C13") (pin "2") (pinfunction "2_2") (pintype "passive"))
      (node (ref "C2") (pin "1") (pinfunction "1_1") (pintype "passive"))
      (node (ref "C20") (pin "1") (pinfunction "1_1") (pintype "passive"))
      (node (ref "C21") (pin "1") (pinfunction "1_1") (pintype "passive"))
      (node (ref "C22") (pin "+") (pinfunction "+_+") (pintype "passive"))
      (node (ref "C23") (pin "+") (pinfunction "+_+") (pintype "passive"))
      (node (ref "C24") (pin "1") (pinfunction "1_1") (pintype "passive"))
      (node (ref "C26") (pin "1") (pinfunction "1_1") (pintype "passive"))
      (node (ref "C28") (pin "1") (pinfunction "1_1") (pintype "passive"))
      (node (ref "C3") (pin "1") (pinfunction "1_1") (pintype "passive"))
      (node (ref "C31") (pin "+") (pinfunction "+_+") (pintype "passive"))
      (node (ref "C32") (pin "+") (pinfunction "+_+") (pintype "passive"))
      (node (ref "C4") (pin "1") (pinfunction "1_1") (pintype "passive"))
      (node (ref "C5") (pin "1") (pinfunction "1_1") (pintype "passive"))
      (node (ref "C6") (pin "1") (pinfunction "1_1") (pintype "passive"))
      (node (ref "C7") (pin "1") (pinfunction "1_1") (pintype "passive"))
      (node (ref "D2") (pin "C") (pinfunction "C_C") (pintype "passive"))
      (node (ref "Q1") (pin "D") (pinfunction "D_D") (pintype "passive"))
      (node (ref "Q3") (pin "D") (pinfunction "D_D") (pintype "passive"))
      (node (ref "Q5") (pin "D") (pinfunction "D_D") (pintype "passive"))
      (node (ref "R1") (pin "2") (pinfunction "2_2") (pintype "passive"))
      (node (ref "U$26") (pin "PAD") (pinfunction "PAD_PAD") (pintype "bidirectional"))
      (node (ref "U2") (pin "29") (pinfunction "PVDD1_29") (pintype "bidirectional"))
      (node (ref "U2") (pin "53") (pinfunction "PVDD2_1_53") (pintype "bidirectional"))
      (node (ref "U2") (pin "54") (pinfunction "PVDD2_2_54") (pintype "bidirectional"))
    )
    (net (code "81") (name "unconnected-(IC1-VREF-Pad5)") (class "Default")
      (node (ref "IC1") (pin "5") (pinfunction "VREF_5") (pintype "output"))
    )
    (net (code "82") (name "unconnected-(U$17-Pad1)") (class "Default")
      (node (ref "U$17") (pin "1") (pinfunction "1_1") (pintype "bidirectional"))
    )
    (net (code "83") (name "unconnected-(U1-PadPGM)") (class "Default")
      (node (ref "U1") (pin "PGM") (pinfunction "PGM_PGM") (pintype "bidirectional"))
    )
    (net (code "84") (name "unconnected-(U1-PadRESET)") (class "Default")
      (node (ref "U1") (pin "RESET") (pinfunction "RESET_RESET") (pintype "bidirectional"))
    )
    (net (code "85") (name "unconnected-(U2-EN_BUCK-Pad55)") (class "Default")
      (node (ref "U2") (pin "55") (pinfunction "EN_BUCK_55") (pintype "bidirectional"))
    )
    (net (code "86") (name "unconnected-(U2-PWRGD-Pad4)") (class "Default")
      (node (ref "U2") (pin "4") (pinfunction "PWRGD_4") (pintype "bidirectional"))
    )
    (net (code "87") (name "unconnected-(U2-{slash}FAULT-Pad6)") (class "Default")
      (node (ref "U2") (pin "6") (pinfunction "/FAULT_6") (pintype "bidirectional"))
    )
    (net (code "88") (name "unconnected-(U2-{slash}OCTW-Pad5)") (class "Default")
      (node (ref "U2") (pin "5") (pinfunction "/OCTW_5") (pintype "bidirectional"))
    )
  )
)
